# 01_Power.net
KiCad netlist of a schematic drawn in Altium Designer
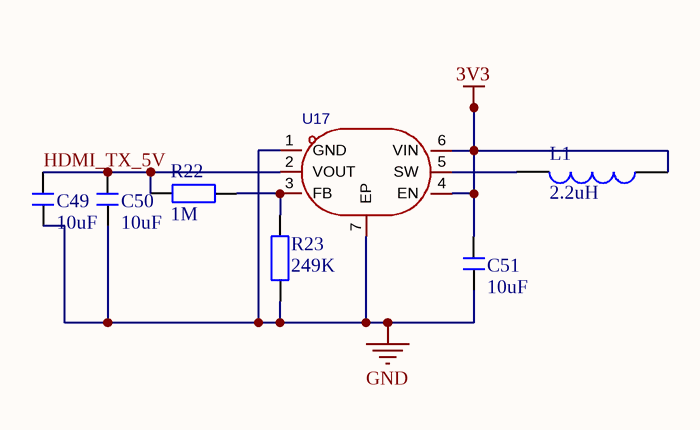
[diagram p0: 01_Power.SchDoc]

(export (version "E")
  (design (tool "Eeschema 10.0.6"))
  (components
    (comp (ref "C49")
      (value "10uF")
      (footprint "C 0603_L")
      (description "贴片电容")
      (libsource (lib "Xilinx_XCKU040_Ext_Board") (part "C"))
    )
    (comp (ref "C50")
      (value "10uF")
      (footprint "C 0603_L")
      (description "贴片电容")
      (libsource (lib "Xilinx_XCKU040_Ext_Board") (part "C"))
    )
    (comp (ref "C51")
      (value "10uF")
      (footprint "C 0603_L")
      (description "贴片电容")
      (libsource (lib "Xilinx_XCKU040_Ext_Board") (part "C"))
    )
    (comp (ref "L1")
      (value "2.2uH")
      (footprint "L")
      (description "小功率贴片电感")
      (libsource (lib "0.1 - 电阻-电容-电感") (part "L"))
    )
    (comp (ref "R22")
      (value "1M")
      (footprint "R 0603_L")
      (description "贴片电阻")
      (fields (field (name "版权归属") "来自淘宝 ID：黄晶宝石"))
      (libsource (lib "Xilinx_XCKU040_Ext_Board") (part "R"))
    )
    (comp (ref "R23")
      (value "249K")
      (footprint "R 0603_L")
      (description "贴片电阻")
      (fields (field (name "版权归属") "来自淘宝 ID：黄晶宝石"))
      (libsource (lib "Xilinx_XCKU040_Ext_Board") (part "R"))
    )
    (comp (ref "U17")
      (value "tps61099drvr")
      (footprint "WSON-6_L2.0-W2.0-P0.65-TL-EP")
      (description "功能类型:升压型;工作电压:700mV~5.5V;输出电压:1.8V~5.5V;输出电流:-;输出类型:可调;")
      (fields (field (name "MANUFACTURER") "TI(德州仪器)") (field (name "MANUFACTURERPART") "TPS61099DRVR"))
      (libsource (lib "Xilinx_XCKU040_Ext_Board") (part "tps61099drvr"))
    )
  )
  (nets
    (net (code "1") (name "/HDMI_TX_5V") (class "Default")
      (node (ref "C49") (pin "2") (pinfunction "2_2") (pintype "passive"))
      (node (ref "C50") (pin "2") (pinfunction "2_2") (pintype "passive"))
      (node (ref "R22") (pin "1") (pinfunction "1_1") (pintype "passive"))
      (node (ref "U17") (pin "2") (pinfunction "VOUT_2") (pintype "passive"))
    )
    (net (code "2") (name "3V3") (class "Default")
      (node (ref "C51") (pin "2") (pinfunction "2_2") (pintype "passive"))
      (node (ref "L1") (pin "1") (pinfunction "1_1") (pintype "passive"))
      (node (ref "U17") (pin "4") (pinfunction "EN_4") (pintype "passive"))
      (node (ref "U17") (pin "6") (pinfunction "VIN_6") (pintype "passive"))
    )
    (net (code "3") (name "GND") (class "Default")
      (node (ref "C49") (pin "1") (pinfunction "1_1") (pintype "passive"))
      (node (ref "C50") (pin "1") (pinfunction "1_1") (pintype "passive"))
      (node (ref "C51") (pin "1") (pinfunction "1_1") (pintype "passive"))
      (node (ref "R23") (pin "1") (pinfunction "1_1") (pintype "passive"))
      (node (ref "U17") (pin "1") (pinfunction "GND_1") (pintype "passive"))
      (node (ref "U17") (pin "7") (pinfunction "EP_7") (pintype "passive"))
    )
    (net (code "4") (name "Net-(U17-FB)") (class "Default")
      (node (ref "R22") (pin "2") (pinfunction "2_2") (pintype "passive"))
      (node (ref "R23") (pin "2") (pinfunction "2_2") (pintype "passive"))
      (node (ref "U17") (pin "3") (pinfunction "FB_3") (pintype "passive"))
    )
    (net (code "5") (name "Net-(U17-SW)") (class "Default")
      (node (ref "L1") (pin "2") (pinfunction "2_2") (pintype "passive"))
      (node (ref "U17") (pin "5") (pinfunction "SW_5") (pintype "passive"))
    )
  )
)
